# Adafruit_SMT_Datalogger_Shield_rev_B.net
KiCad netlist of a schematic drawn in EAGLE
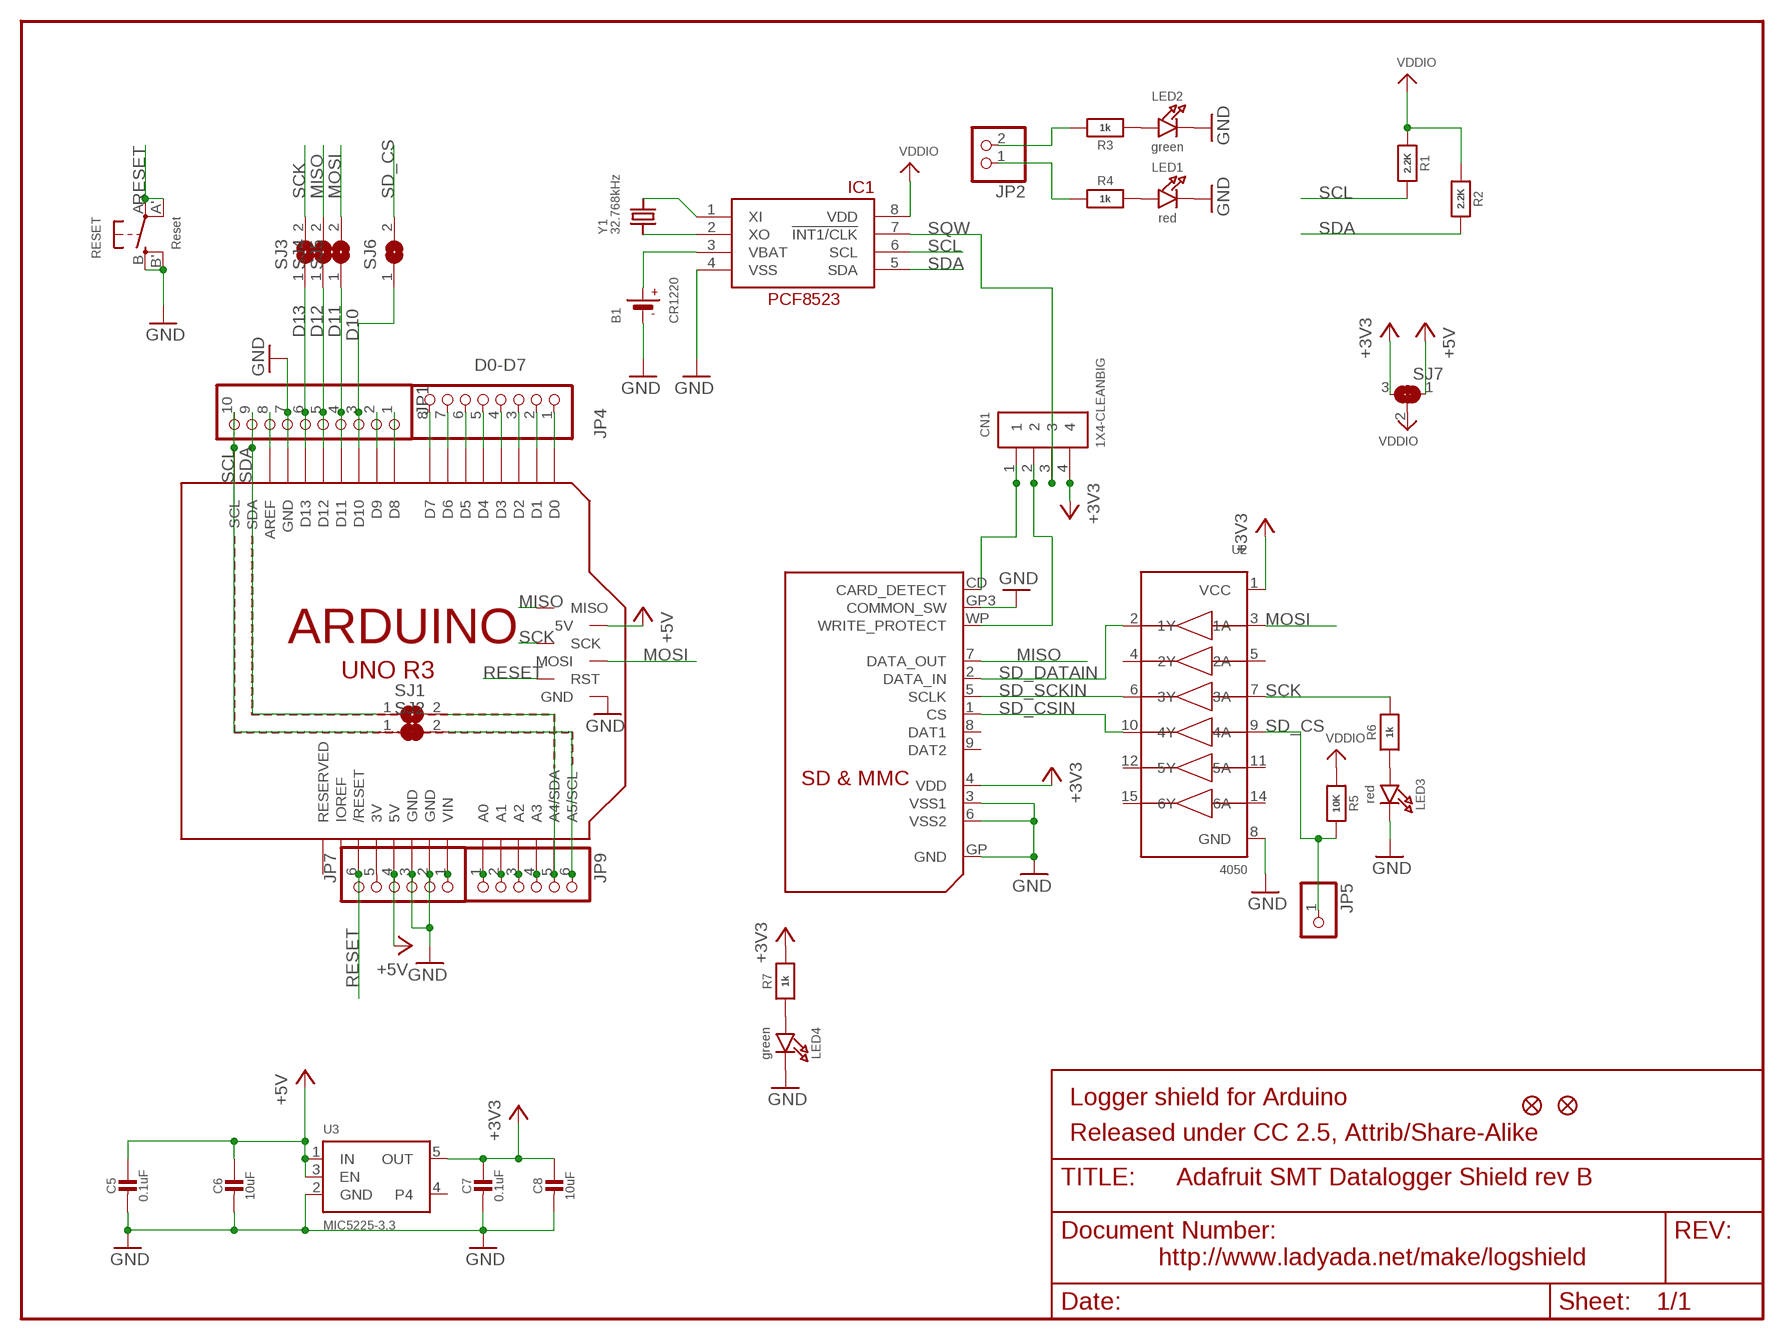
[diagram p0: schematic, sheet 1]

(export (version "E")
  (design (tool "Eeschema 10.0.6"))
  (components
    (comp (ref "B1")
      (value "CR1220")
      (footprint "eagle-import:CR1220")
      (libsource (lib "eagle-import") (part "BATTERYCR1220_SMT"))
    )
    (comp (ref "C5")
      (value "0.1uF")
      (footprint "eagle-import:0805-NO")
      (libsource (lib "eagle-import") (part "CAP_CERAMIC0805-NOOUTLINE"))
    )
    (comp (ref "C6")
      (value "10uF")
      (footprint "eagle-import:0805-NO")
      (libsource (lib "eagle-import") (part "CAP_CERAMIC0805-NOOUTLINE"))
    )
    (comp (ref "C7")
      (value "0.1uF")
      (footprint "eagle-import:0805-NO")
      (libsource (lib "eagle-import") (part "CAP_CERAMIC0805-NOOUTLINE"))
    )
    (comp (ref "C8")
      (value "10uF")
      (footprint "eagle-import:0805-NO")
      (libsource (lib "eagle-import") (part "CAP_CERAMIC0805-NOOUTLINE"))
    )
    (comp (ref "CN1")
      (value "1X4-CLEANBIG")
      (footprint "eagle-import:1X04-CLEANBIG")
      (libsource (lib "eagle-import") (part "1X4-CLEANBIG"))
    )
    (comp (ref "FID1")
      (value "FIDUCIAL\"\"")
      (footprint "eagle-import:FIDUCIAL_1MM")
      (libsource (lib "eagle-import") (part "FIDUCIAL{dblquote}{dblquote}"))
    )
    (comp (ref "FID3")
      (value "FIDUCIAL\"\"")
      (footprint "eagle-import:FIDUCIAL_1MM")
      (libsource (lib "eagle-import") (part "FIDUCIAL{dblquote}{dblquote}"))
    )
    (comp (ref "IC1")
      (value "RTC_PCF8523T")
      (footprint "eagle-import:SOIC8_150MIL")
      (libsource (lib "eagle-import") (part "RTC_PCF8523T"))
    )
    (comp (ref "JP1")
      (value "HEADER-1X1070MIL")
      (footprint "eagle-import:1X10_ROUND70")
      (libsource (lib "eagle-import") (part "HEADER-1X1070MIL"))
    )
    (comp (ref "JP2")
      (value "HEADER-1X2ROUND")
      (footprint "eagle-import:1X02_ROUND")
      (libsource (lib "eagle-import") (part "HEADER-1X2ROUND"))
    )
    (comp (ref "JP4")
      (value "D0-D7")
      (footprint "eagle-import:1X08-BIG")
      (libsource (lib "eagle-import") (part "PINHD-1X8BIG"))
    )
    (comp (ref "JP5")
      (value "HEADER-1X1ROUND")
      (footprint "eagle-import:1X01_ROUND")
      (libsource (lib "eagle-import") (part "HEADER-1X1ROUND"))
    )
    (comp (ref "JP7")
      (value "PINHD-1X6B")
      (footprint "eagle-import:1X06-BIG")
      (libsource (lib "eagle-import") (part "PINHD-1X6B"))
    )
    (comp (ref "JP9")
      (value "PINHD-1X6B")
      (footprint "eagle-import:1X06-BIG")
      (libsource (lib "eagle-import") (part "PINHD-1X6B"))
    )
    (comp (ref "LED1")
      (value "red")
      (footprint "eagle-import:CHIPLED_0805_NOOUTLINE")
      (libsource (lib "eagle-import") (part "LED0805_NOOUTLINE"))
    )
    (comp (ref "LED2")
      (value "green")
      (footprint "eagle-import:CHIPLED_0805_NOOUTLINE")
      (libsource (lib "eagle-import") (part "LED0805_NOOUTLINE"))
    )
    (comp (ref "LED3")
      (value "red")
      (footprint "eagle-import:CHIPLED_0805_NOOUTLINE")
      (libsource (lib "eagle-import") (part "LED0805_NOOUTLINE"))
    )
    (comp (ref "LED4")
      (value "green")
      (footprint "eagle-import:CHIPLED_0805_NOOUTLINE")
      (libsource (lib "eagle-import") (part "LED0805_NOOUTLINE"))
    )
    (comp (ref "M1")
      (value "ARDUINO_R3_ICSP")
      (footprint "eagle-import:ARDUINOR3_ICSP")
      (libsource (lib "eagle-import") (part "ARDUINO_R3_ICSP"))
    )
    (comp (ref "R1")
      (value "2.2K")
      (footprint "eagle-import:0805-NO")
      (libsource (lib "eagle-import") (part "RESISTOR0805_NOOUTLINE"))
    )
    (comp (ref "R2")
      (value "2.2K")
      (footprint "eagle-import:0805-NO")
      (libsource (lib "eagle-import") (part "RESISTOR0805_NOOUTLINE"))
    )
    (comp (ref "R3")
      (value "1k")
      (footprint "eagle-import:0805-NO")
      (libsource (lib "eagle-import") (part "RESISTOR0805_NOOUTLINE"))
    )
    (comp (ref "R4")
      (value "1k")
      (footprint "eagle-import:0805-NO")
      (libsource (lib "eagle-import") (part "RESISTOR0805_NOOUTLINE"))
    )
    (comp (ref "R5")
      (value "10K")
      (footprint "eagle-import:0805-NO")
      (libsource (lib "eagle-import") (part "RESISTOR0805_NOOUTLINE"))
    )
    (comp (ref "R6")
      (value "1k")
      (footprint "eagle-import:0805-NO")
      (libsource (lib "eagle-import") (part "RESISTOR0805_NOOUTLINE"))
    )
    (comp (ref "R7")
      (value "1k")
      (footprint "eagle-import:0805-NO")
      (libsource (lib "eagle-import") (part "RESISTOR0805_NOOUTLINE"))
    )
    (comp (ref "RESET")
      (value "Reset")
      (footprint "eagle-import:EVQ-Q2")
      (libsource (lib "eagle-import") (part "SWITCH_TACT_SMT"))
    )
    (comp (ref "SJ1")
      (value "SOLDERJUMPER")
      (footprint "eagle-import:SOLDERJUMPER_ARROW_NOPASTE")
      (libsource (lib "eagle-import") (part "SOLDERJUMPER"))
    )
    (comp (ref "SJ2")
      (value "SOLDERJUMPER")
      (footprint "eagle-import:SOLDERJUMPER_ARROW_NOPASTE")
      (libsource (lib "eagle-import") (part "SOLDERJUMPER"))
    )
    (comp (ref "SJ3")
      (value "SOLDERJUMPER")
      (footprint "eagle-import:SOLDERJUMPER_ARROW_NOPASTE")
      (libsource (lib "eagle-import") (part "SOLDERJUMPER"))
    )
    (comp (ref "SJ4")
      (value "SOLDERJUMPER")
      (footprint "eagle-import:SOLDERJUMPER_ARROW_NOPASTE")
      (libsource (lib "eagle-import") (part "SOLDERJUMPER"))
    )
    (comp (ref "SJ5")
      (value "SOLDERJUMPER")
      (footprint "eagle-import:SOLDERJUMPER_ARROW_NOPASTE")
      (libsource (lib "eagle-import") (part "SOLDERJUMPER"))
    )
    (comp (ref "SJ6")
      (value "SOLDERJUMPERCLOSED")
      (footprint "eagle-import:SOLDERJUMPER_CLOSEDWIRE")
      (libsource (lib "eagle-import") (part "SOLDERJUMPERCLOSED"))
    )
    (comp (ref "SJ7")
      (value "SOLDERJUMPER_2WAY")
      (footprint "eagle-import:SOLDERJUMPER_2WAY_OPEN_NOPASTE")
      (libsource (lib "eagle-import") (part "SOLDERJUMPER_2WAY"))
    )
    (comp (ref "U$2")
      (value "SDMMC06132")
      (footprint "eagle-import:06132")
      (libsource (lib "eagle-import") (part "SDMMC06132"))
    )
    (comp (ref "U2")
      (value "4050")
      (footprint "eagle-import:SOIC16")
      (libsource (lib "eagle-import") (part "74HC4050D"))
    )
    (comp (ref "U3")
      (value "MIC5225-3.3")
      (footprint "eagle-import:SOT23-5")
      (libsource (lib "eagle-import") (part "VREG_SOT23-5"))
    )
    (comp (ref "Y1")
      (value "32.768kHz")
      (footprint "eagle-import:CRYSTAL_8X3.8")
      (libsource (lib "eagle-import") (part "CRYSTAL8.0X3.8"))
    )
  )
  (nets
    (net (code "1") (name "+3V3") (class "Default")
      (node (ref "C7") (pin "1") (pinfunction "1_1") (pintype "passive"))
      (node (ref "C8") (pin "1") (pinfunction "1_1") (pintype "passive"))
      (node (ref "CN1") (pin "4") (pinfunction "4_4") (pintype "bidirectional"))
      (node (ref "R7") (pin "2") (pinfunction "2_2") (pintype "passive"))
      (node (ref "SJ7") (pin "3") (pinfunction "3_3") (pintype "passive"))
      (node (ref "U$2") (pin "4") (pinfunction "VDD_4") (pintype "power_in"))
      (node (ref "U2") (pin "1") (pinfunction "VCC_1") (pintype "bidirectional"))
      (node (ref "U3") (pin "5") (pinfunction "OUT_5") (pintype "power_in"))
    )
    (net (code "2") (name "+5V") (class "Default")
      (node (ref "C5") (pin "1") (pinfunction "1_1") (pintype "passive"))
      (node (ref "C6") (pin "1") (pinfunction "1_1") (pintype "passive"))
      (node (ref "JP7") (pin "4") (pinfunction "4_4") (pintype "passive"))
      (node (ref "M1") (pin "5V") (pinfunction "5V_5V") (pintype "power_in"))
      (node (ref "M1") (pin "5V_ICSP") (pinfunction "5V_5V_ICSP") (pintype "passive"))
      (node (ref "SJ7") (pin "1") (pinfunction "1_1") (pintype "passive"))
      (node (ref "U3") (pin "1") (pinfunction "IN_1") (pintype "power_in"))
      (node (ref "U3") (pin "3") (pinfunction "EN_3") (pintype "input"))
    )
    (net (code "3") (name "/D10") (class "Default")
      (node (ref "JP1") (pin "3") (pinfunction "3_3") (pintype "passive"))
      (node (ref "M1") (pin "D10") (pinfunction "D10_D10") (pintype "bidirectional"))
      (node (ref "SJ6") (pin "1") (pinfunction "1_1") (pintype "passive"))
    )
    (net (code "4") (name "/D11") (class "Default")
      (node (ref "JP1") (pin "4") (pinfunction "4_4") (pintype "passive"))
      (node (ref "M1") (pin "D11") (pinfunction "D11_D11") (pintype "bidirectional"))
      (node (ref "SJ5") (pin "1") (pinfunction "1_1") (pintype "passive"))
    )
    (net (code "5") (name "/D12") (class "Default")
      (node (ref "JP1") (pin "5") (pinfunction "5_5") (pintype "passive"))
      (node (ref "M1") (pin "D12") (pinfunction "D12_D12") (pintype "bidirectional"))
      (node (ref "SJ4") (pin "1") (pinfunction "1_1") (pintype "passive"))
    )
    (net (code "6") (name "/D13") (class "Default")
      (node (ref "JP1") (pin "6") (pinfunction "6_6") (pintype "passive"))
      (node (ref "M1") (pin "D13") (pinfunction "D13_D13") (pintype "bidirectional"))
      (node (ref "SJ3") (pin "1") (pinfunction "1_1") (pintype "passive"))
    )
    (net (code "7") (name "/MISO") (class "Default")
      (node (ref "M1") (pin "MISO") (pinfunction "MISO_MISO") (pintype "passive"))
      (node (ref "SJ4") (pin "2") (pinfunction "2_2") (pintype "passive"))
      (node (ref "U$2") (pin "7") (pinfunction "DATA_OUT_7") (pintype "output"))
    )
    (net (code "8") (name "/MOSI") (class "Default")
      (node (ref "M1") (pin "MOSI") (pinfunction "MOSI_MOSI") (pintype "passive"))
      (node (ref "SJ5") (pin "2") (pinfunction "2_2") (pintype "passive"))
      (node (ref "U2") (pin "3") (pinfunction "1A_3") (pintype "bidirectional"))
    )
    (net (code "9") (name "/RESET") (class "Default")
      (node (ref "JP7") (pin "6") (pinfunction "6_6") (pintype "passive"))
      (node (ref "M1") (pin "RESET") (pinfunction "/RESET_RESET") (pintype "bidirectional"))
      (node (ref "M1") (pin "RESET_ICSP") (pinfunction "RST_RESET_ICSP") (pintype "passive"))
      (node (ref "RESET") (pin "A") (pinfunction "P_A") (pintype "passive"))
      (node (ref "RESET") (pin "A'") (pinfunction "P1_A'") (pintype "passive"))
    )
    (net (code "10") (name "/SCK") (class "Default")
      (node (ref "M1") (pin "SCK") (pinfunction "SCK_SCK") (pintype "passive"))
      (node (ref "R6") (pin "2") (pinfunction "2_2") (pintype "passive"))
      (node (ref "SJ3") (pin "2") (pinfunction "2_2") (pintype "passive"))
      (node (ref "U2") (pin "7") (pinfunction "3A_7") (pintype "bidirectional"))
    )
    (net (code "11") (name "/SCL") (class "Default")
      (node (ref "IC1") (pin "6") (pinfunction "SCL_6") (pintype "bidirectional"))
      (node (ref "JP1") (pin "10") (pinfunction "10_10") (pintype "passive"))
      (node (ref "M1") (pin "SCL") (pinfunction "SCL_SCL") (pintype "bidirectional"))
      (node (ref "R1") (pin "2") (pinfunction "2_2") (pintype "passive"))
      (node (ref "SJ2") (pin "1") (pinfunction "1_1") (pintype "passive"))
    )
    (net (code "12") (name "/SDA") (class "Default")
      (node (ref "IC1") (pin "5") (pinfunction "SDA_5") (pintype "bidirectional"))
      (node (ref "JP1") (pin "9") (pinfunction "9_9") (pintype "passive"))
      (node (ref "M1") (pin "SDA") (pinfunction "SDA_SDA") (pintype "bidirectional"))
      (node (ref "R2") (pin "2") (pinfunction "2_2") (pintype "passive"))
      (node (ref "SJ1") (pin "1") (pinfunction "1_1") (pintype "passive"))
    )
    (net (code "13") (name "/SD_CS") (class "Default")
      (node (ref "JP5") (pin "1") (pinfunction "1_1") (pintype "passive"))
      (node (ref "R5") (pin "2") (pinfunction "2_2") (pintype "passive"))
      (node (ref "SJ6") (pin "2") (pinfunction "2_2") (pintype "passive"))
      (node (ref "U2") (pin "9") (pinfunction "4A_9") (pintype "bidirectional"))
    )
    (net (code "14") (name "/SD_CSIN") (class "Default")
      (node (ref "U$2") (pin "1") (pinfunction "CS_1") (pintype "input"))
      (node (ref "U2") (pin "10") (pinfunction "4Y_10") (pintype "bidirectional"))
    )
    (net (code "15") (name "/SD_DATAIN") (class "Default")
      (node (ref "U$2") (pin "2") (pinfunction "DATA_IN_2") (pintype "input"))
      (node (ref "U2") (pin "2") (pinfunction "1Y_2") (pintype "bidirectional"))
    )
    (net (code "16") (name "/SD_SCKIN") (class "Default")
      (node (ref "U$2") (pin "5") (pinfunction "SCLK_5") (pintype "input"))
      (node (ref "U2") (pin "6") (pinfunction "3Y_6") (pintype "bidirectional"))
    )
    (net (code "17") (name "/SQW") (class "Default")
      (node (ref "CN1") (pin "3") (pinfunction "3_3") (pintype "bidirectional"))
      (node (ref "IC1") (pin "7") (pinfunction "~{INT1/CLK}_7") (pintype "output"))
    )
    (net (code "18") (name "GND") (class "Default")
      (node (ref "B1") (pin "-") (pinfunction "-_-") (pintype "passive"))
      (node (ref "C5") (pin "2") (pinfunction "2_2") (pintype "passive"))
      (node (ref "C6") (pin "2") (pinfunction "2_2") (pintype "passive"))
      (node (ref "C7") (pin "2") (pinfunction "2_2") (pintype "passive"))
      (node (ref "C8") (pin "2") (pinfunction "2_2") (pintype "passive"))
      (node (ref "IC1") (pin "4") (pinfunction "VSS_4") (pintype "power_in"))
      (node (ref "JP1") (pin "7") (pinfunction "7_7") (pintype "passive"))
      (node (ref "JP7") (pin "2") (pinfunction "2_2") (pintype "passive"))
      (node (ref "JP7") (pin "3") (pinfunction "3_3") (pintype "passive"))
      (node (ref "LED1") (pin "C") (pinfunction "C_C") (pintype "passive"))
      (node (ref "LED2") (pin "C") (pinfunction "C_C") (pintype "passive"))
      (node (ref "LED3") (pin "C") (pinfunction "C_C") (pintype "passive"))
      (node (ref "LED4") (pin "C") (pinfunction "C_C") (pintype "passive"))
      (node (ref "M1") (pin "GND") (pinfunction "GND_GND") (pintype "power_in"))
      (node (ref "M1") (pin "GND@1") (pinfunction "GND_GND@1") (pintype "power_in"))
      (node (ref "M1") (pin "GND@2") (pinfunction "GND_GND@2") (pintype "passive"))
      (node (ref "M1") (pin "GND@3") (pinfunction "GND_GND@3") (pintype "power_in"))
      (node (ref "RESET") (pin "B") (pinfunction "S_B") (pintype "passive"))
      (node (ref "RESET") (pin "B'") (pinfunction "S1_B'") (pintype "passive"))
      (node (ref "U$2") (pin "3") (pinfunction "VSS1_3") (pintype "power_in"))
      (node (ref "U$2") (pin "6") (pinfunction "VSS2_6") (pintype "power_in"))
      (node (ref "U$2") (pin "GP") (pinfunction "GND_GP") (pintype "power_in"))
      (node (ref "U$2") (pin "GP3") (pinfunction "COMMON_SW_GP3") (pintype "passive"))
      (node (ref "U2") (pin "8") (pinfunction "GND_8") (pintype "bidirectional"))
      (node (ref "U3") (pin "2") (pinfunction "GND_2") (pintype "power_in"))
    )
    (net (code "19") (name "Net-(B1-+)") (class "Default")
      (node (ref "B1") (pin "+$1") (pinfunction "+_+$1") (pintype "passive"))
      (node (ref "IC1") (pin "3") (pinfunction "VBAT_3") (pintype "power_in"))
    )
    (net (code "20") (name "Net-(IC1-XI)") (class "Default")
      (node (ref "IC1") (pin "1") (pinfunction "XI_1") (pintype "input"))
      (node (ref "Y1") (pin "P$4") (pinfunction "2_P$4") (pintype "passive"))
    )
    (net (code "21") (name "Net-(IC1-XO)") (class "Default")
      (node (ref "IC1") (pin "2") (pinfunction "XO_2") (pintype "output"))
      (node (ref "Y1") (pin "P$1") (pinfunction "1_P$1") (pintype "passive"))
    )
    (net (code "22") (name "Net-(JP1-Pad1)") (class "Default")
      (node (ref "JP1") (pin "1") (pinfunction "1_1") (pintype "passive"))
      (node (ref "M1") (pin "D8") (pinfunction "D8_D8") (pintype "bidirectional"))
    )
    (net (code "23") (name "Net-(JP1-Pad2)") (class "Default")
      (node (ref "JP1") (pin "2") (pinfunction "2_2") (pintype "passive"))
      (node (ref "M1") (pin "D9") (pinfunction "D9_D9") (pintype "bidirectional"))
    )
    (net (code "24") (name "Net-(JP1-Pad8)") (class "Default")
      (node (ref "JP1") (pin "8") (pinfunction "8_8") (pintype "passive"))
      (node (ref "M1") (pin "AREF") (pinfunction "AREF_AREF") (pintype "bidirectional"))
    )
    (net (code "25") (name "Net-(JP2-Pad1)") (class "Default")
      (node (ref "JP2") (pin "1") (pinfunction "1_1") (pintype "passive"))
      (node (ref "R4") (pin "1") (pinfunction "1_1") (pintype "passive"))
    )
    (net (code "26") (name "Net-(JP2-Pad2)") (class "Default")
      (node (ref "JP2") (pin "2") (pinfunction "2_2") (pintype "passive"))
      (node (ref "R3") (pin "2") (pinfunction "2_2") (pintype "passive"))
    )
    (net (code "27") (name "Net-(JP4-Pad1)") (class "Default")
      (node (ref "JP4") (pin "1") (pinfunction "1_1") (pintype "passive"))
      (node (ref "M1") (pin "D0") (pinfunction "D0_D0") (pintype "bidirectional"))
    )
    (net (code "28") (name "Net-(JP4-Pad2)") (class "Default")
      (node (ref "JP4") (pin "2") (pinfunction "2_2") (pintype "passive"))
      (node (ref "M1") (pin "D1") (pinfunction "D1_D1") (pintype "bidirectional"))
    )
    (net (code "29") (name "Net-(JP4-Pad3)") (class "Default")
      (node (ref "JP4") (pin "3") (pinfunction "3_3") (pintype "passive"))
      (node (ref "M1") (pin "D2") (pinfunction "D2_D2") (pintype "bidirectional"))
    )
    (net (code "30") (name "Net-(JP4-Pad4)") (class "Default")
      (node (ref "JP4") (pin "4") (pinfunction "4_4") (pintype "passive"))
      (node (ref "M1") (pin "D3") (pinfunction "D3_D3") (pintype "bidirectional"))
    )
    (net (code "31") (name "Net-(JP4-Pad5)") (class "Default")
      (node (ref "JP4") (pin "5") (pinfunction "5_5") (pintype "passive"))
      (node (ref "M1") (pin "D4") (pinfunction "D4_D4") (pintype "bidirectional"))
    )
    (net (code "32") (name "Net-(JP4-Pad6)") (class "Default")
      (node (ref "JP4") (pin "6") (pinfunction "6_6") (pintype "passive"))
      (node (ref "M1") (pin "D5") (pinfunction "D5_D5") (pintype "bidirectional"))
    )
    (net (code "33") (name "Net-(JP4-Pad7)") (class "Default")
      (node (ref "JP4") (pin "7") (pinfunction "7_7") (pintype "passive"))
      (node (ref "M1") (pin "D6") (pinfunction "D6_D6") (pintype "bidirectional"))
    )
    (net (code "34") (name "Net-(JP4-Pad8)") (class "Default")
      (node (ref "JP4") (pin "8") (pinfunction "8_8") (pintype "passive"))
      (node (ref "M1") (pin "D7") (pinfunction "D7_D7") (pintype "bidirectional"))
    )
    (net (code "35") (name "Net-(JP7-Pad1)") (class "Default")
      (node (ref "JP7") (pin "1") (pinfunction "1_1") (pintype "passive"))
      (node (ref "M1") (pin "VIN") (pinfunction "VIN_VIN") (pintype "power_in"))
    )
    (net (code "36") (name "Net-(JP7-Pad5)") (class "Default")
      (node (ref "JP7") (pin "5") (pinfunction "5_5") (pintype "passive"))
      (node (ref "M1") (pin "3V") (pinfunction "3V_3V") (pintype "power_in"))
    )
    (net (code "37") (name "Net-(JP9-Pad1)") (class "Default")
      (node (ref "JP9") (pin "1") (pinfunction "1_1") (pintype "passive"))
      (node (ref "M1") (pin "A0") (pinfunction "A0_A0") (pintype "bidirectional"))
    )
    (net (code "38") (name "Net-(JP9-Pad2)") (class "Default")
      (node (ref "JP9") (pin "2") (pinfunction "2_2") (pintype "passive"))
      (node (ref "M1") (pin "A1") (pinfunction "A1_A1") (pintype "bidirectional"))
    )
    (net (code "39") (name "Net-(JP9-Pad3)") (class "Default")
      (node (ref "JP9") (pin "3") (pinfunction "3_3") (pintype "passive"))
      (node (ref "M1") (pin "A2") (pinfunction "A2_A2") (pintype "bidirectional"))
    )
    (net (code "40") (name "Net-(JP9-Pad4)") (class "Default")
      (node (ref "JP9") (pin "4") (pinfunction "4_4") (pintype "passive"))
      (node (ref "M1") (pin "A3") (pinfunction "A3_A3") (pintype "bidirectional"))
    )
    (net (code "41") (name "Net-(LED1-PadA)") (class "Default")
      (node (ref "LED1") (pin "A") (pinfunction "A_A") (pintype "passive"))
      (node (ref "R4") (pin "2") (pinfunction "2_2") (pintype "passive"))
    )
    (net (code "42") (name "Net-(LED2-PadA)") (class "Default")
      (node (ref "LED2") (pin "A") (pinfunction "A_A") (pintype "passive"))
      (node (ref "R3") (pin "1") (pinfunction "1_1") (pintype "passive"))
    )
    (net (code "43") (name "Net-(LED3-PadA)") (class "Default")
      (node (ref "LED3") (pin "A") (pinfunction "A_A") (pintype "passive"))
      (node (ref "R6") (pin "1") (pinfunction "1_1") (pintype "passive"))
    )
    (net (code "44") (name "Net-(LED4-PadA)") (class "Default")
      (node (ref "LED4") (pin "A") (pinfunction "A_A") (pintype "passive"))
      (node (ref "R7") (pin "1") (pinfunction "1_1") (pintype "passive"))
    )
    (net (code "45") (name "Net-(M1-A4{slash}SDA)") (class "Default")
      (node (ref "JP9") (pin "5") (pinfunction "5_5") (pintype "passive"))
      (node (ref "M1") (pin "A4") (pinfunction "A4/SDA_A4") (pintype "bidirectional"))
      (node (ref "SJ1") (pin "2") (pinfunction "2_2") (pintype "passive"))
    )
    (net (code "46") (name "Net-(M1-A5{slash}SCL)") (class "Default")
      (node (ref "JP9") (pin "6") (pinfunction "6_6") (pintype "passive"))
      (node (ref "M1") (pin "A5") (pinfunction "A5/SCL_A5") (pintype "bidirectional"))
      (node (ref "SJ2") (pin "2") (pinfunction "2_2") (pintype "passive"))
    )
    (net (code "47") (name "Net-(U$2-CARD_DETECT)") (class "Default")
      (node (ref "CN1") (pin "1") (pinfunction "1_1") (pintype "bidirectional"))
      (node (ref "U$2") (pin "CD") (pinfunction "CARD_DETECT_CD") (pintype "passive"))
    )
    (net (code "48") (name "Net-(U$2-WRITE_PROTECT)") (class "Default")
      (node (ref "CN1") (pin "2") (pinfunction "2_2") (pintype "bidirectional"))
      (node (ref "U$2") (pin "WP") (pinfunction "WRITE_PROTECT_WP") (pintype "passive"))
    )
    (net (code "49") (name "VDDIO") (class "Default")
      (node (ref "IC1") (pin "8") (pinfunction "VDD_8") (pintype "power_in"))
      (node (ref "R1") (pin "1") (pinfunction "1_1") (pintype "passive"))
      (node (ref "R2") (pin "1") (pinfunction "1_1") (pintype "passive"))
      (node (ref "R5") (pin "1") (pinfunction "1_1") (pintype "passive"))
      (node (ref "SJ7") (pin "2") (pinfunction "2_2") (pintype "passive"))
    )
    (net (code "50") (name "unconnected-(M1-PadIOREF)") (class "Default")
      (node (ref "M1") (pin "IOREF") (pinfunction "IOREF_IOREF") (pintype "output"))
    )
    (net (code "51") (name "unconnected-(M1-PadRESERVED)") (class "Default")
      (node (ref "M1") (pin "RESERVED") (pinfunction "RESERVED_RESERVED") (pintype "no_connect"))
    )
    (net (code "52") (name "unconnected-(U$2-DAT1-Pad8)") (class "Default")
      (node (ref "U$2") (pin "8") (pinfunction "DAT1_8") (pintype "bidirectional"))
    )
    (net (code "53") (name "unconnected-(U$2-DAT2-Pad9)") (class "Default")
      (node (ref "U$2") (pin "9") (pinfunction "DAT2_9") (pintype "bidirectional"))
    )
    (net (code "54") (name "unconnected-(U2-2A-Pad5)") (class "Default")
      (node (ref "U2") (pin "5") (pinfunction "2A_5") (pintype "bidirectional"))
    )
    (net (code "55") (name "unconnected-(U2-2Y-Pad4)") (class "Default")
      (node (ref "U2") (pin "4") (pinfunction "2Y_4") (pintype "bidirectional"))
    )
    (net (code "56") (name "unconnected-(U2-5A-Pad11)") (class "Default")
      (node (ref "U2") (pin "11") (pinfunction "5A_11") (pintype "bidirectional"))
    )
    (net (code "57") (name "unconnected-(U2-5Y-Pad12)") (class "Default")
      (node (ref "U2") (pin "12") (pinfunction "5Y_12") (pintype "bidirectional"))
    )
    (net (code "58") (name "unconnected-(U2-6A-Pad14)") (class "Default")
      (node (ref "U2") (pin "14") (pinfunction "6A_14") (pintype "bidirectional"))
    )
    (net (code "59") (name "unconnected-(U2-6Y-Pad15)") (class "Default")
      (node (ref "U2") (pin "15") (pinfunction "6Y_15") (pintype "bidirectional"))
    )
    (net (code "60") (name "unconnected-(U3-P4-Pad4)") (class "Default")
      (node (ref "U3") (pin "4") (pinfunction "P4_4") (pintype "bidirectional"))
    )
  )
)
